# Line_12V.net
KiCad netlist of a schematic drawn in Altium Designer
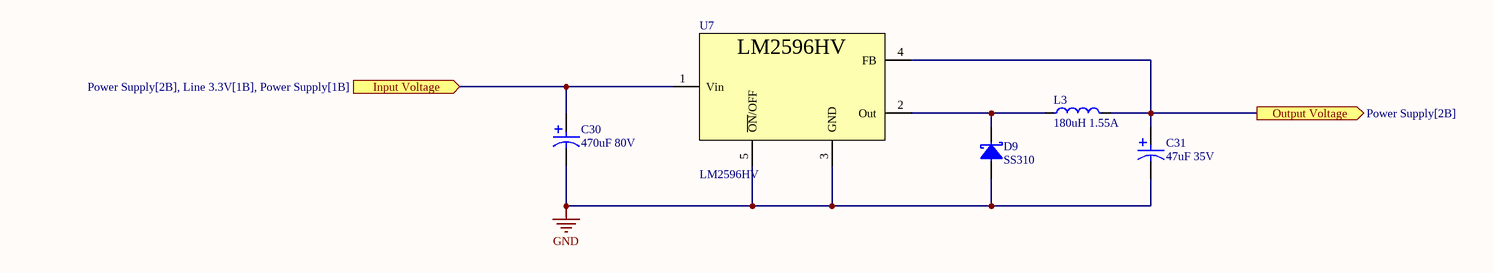
[diagram p0: Line 12V.SchDoc]

(export (version "E")
  (design (tool "Eeschema 10.0.6"))
  (components
    (comp (ref "C30")
      (value "470uF 80V")
      (footprint "BAR CAP 18x16.5")
      (description "EEVFK1K471M 470uF 80V ±20% (18 X 16.5mm)")
      (libsource (lib "Altium_Library") (part "Capacitor 470uF 80V (18x16.5mm)"))
    )
    (comp (ref "C31")
      (value "47uF 35V")
      (footprint "BAR CAP 6.3x5.4")
      (description "47uF 35V 6.3Х5.4mm")
      (libsource (lib "Altium_Library") (part "Capacitor 47uF 35V (6.3x5.4mm)"))
    )
    (comp (ref "D9")
      (value "SS310")
      (footprint "DIODE: SMB")
      (description "100B 3.0A Schottky diode")
      (libsource (lib "Altium_Library") (part "Schottky diode SS310"))
    )
    (comp (ref "L3")
      (value "180uH 1.55A")
      (footprint "Inductor 12x12x8")
      (description "CDRH127/LDNP-181MC 180uH ±20% 1.55A 0.23Ohm")
      (libsource (lib "Altium_Library") (part "Inductor 180uH 1.55A"))
    )
    (comp (ref "U7")
      (value "LM2596HV")
      (footprint "TO-263-5L")
      (description "3A Step-Down Voltage Regulator")
      (libsource (lib "Altium_Library") (part "DC/DC Buck LM2596HV"))
    )
  )
  (nets
    (net (code "1") (name "/Input Voltage") (class "Default")
      (node (ref "C30") (pin "2") (pinfunction "2_2") (pintype "passive"))
      (node (ref "U7") (pin "1") (pinfunction "Vin_1") (pintype "passive"))
    )
    (net (code "2") (name "/Output Voltage") (class "Default")
      (node (ref "C31") (pin "2") (pinfunction "2_2") (pintype "passive"))
      (node (ref "L3") (pin "2") (pinfunction "2_2") (pintype "passive"))
      (node (ref "U7") (pin "4") (pinfunction "FB_4") (pintype "passive"))
    )
    (net (code "3") (name "GND") (class "Default")
      (node (ref "C30") (pin "1") (pinfunction "1_1") (pintype "passive"))
      (node (ref "C31") (pin "1") (pinfunction "1_1") (pintype "passive"))
      (node (ref "D9") (pin "1") (pinfunction "1_1") (pintype "passive"))
      (node (ref "U7") (pin "3") (pinfunction "GND_3") (pintype "passive"))
      (node (ref "U7") (pin "5") (pinfunction "~{ON}/OFF_5") (pintype "passive"))
    )
    (net (code "4") (name "Net-(U7-Out)") (class "Default")
      (node (ref "D9") (pin "2") (pinfunction "2_2") (pintype "passive"))
      (node (ref "L3") (pin "1") (pinfunction "1_1") (pintype "passive"))
      (node (ref "U7") (pin "2") (pinfunction "Out_2") (pintype "passive"))
    )
  )
)
